# design.net
KiCad netlist of a schematic drawn in EasyEDA Pro
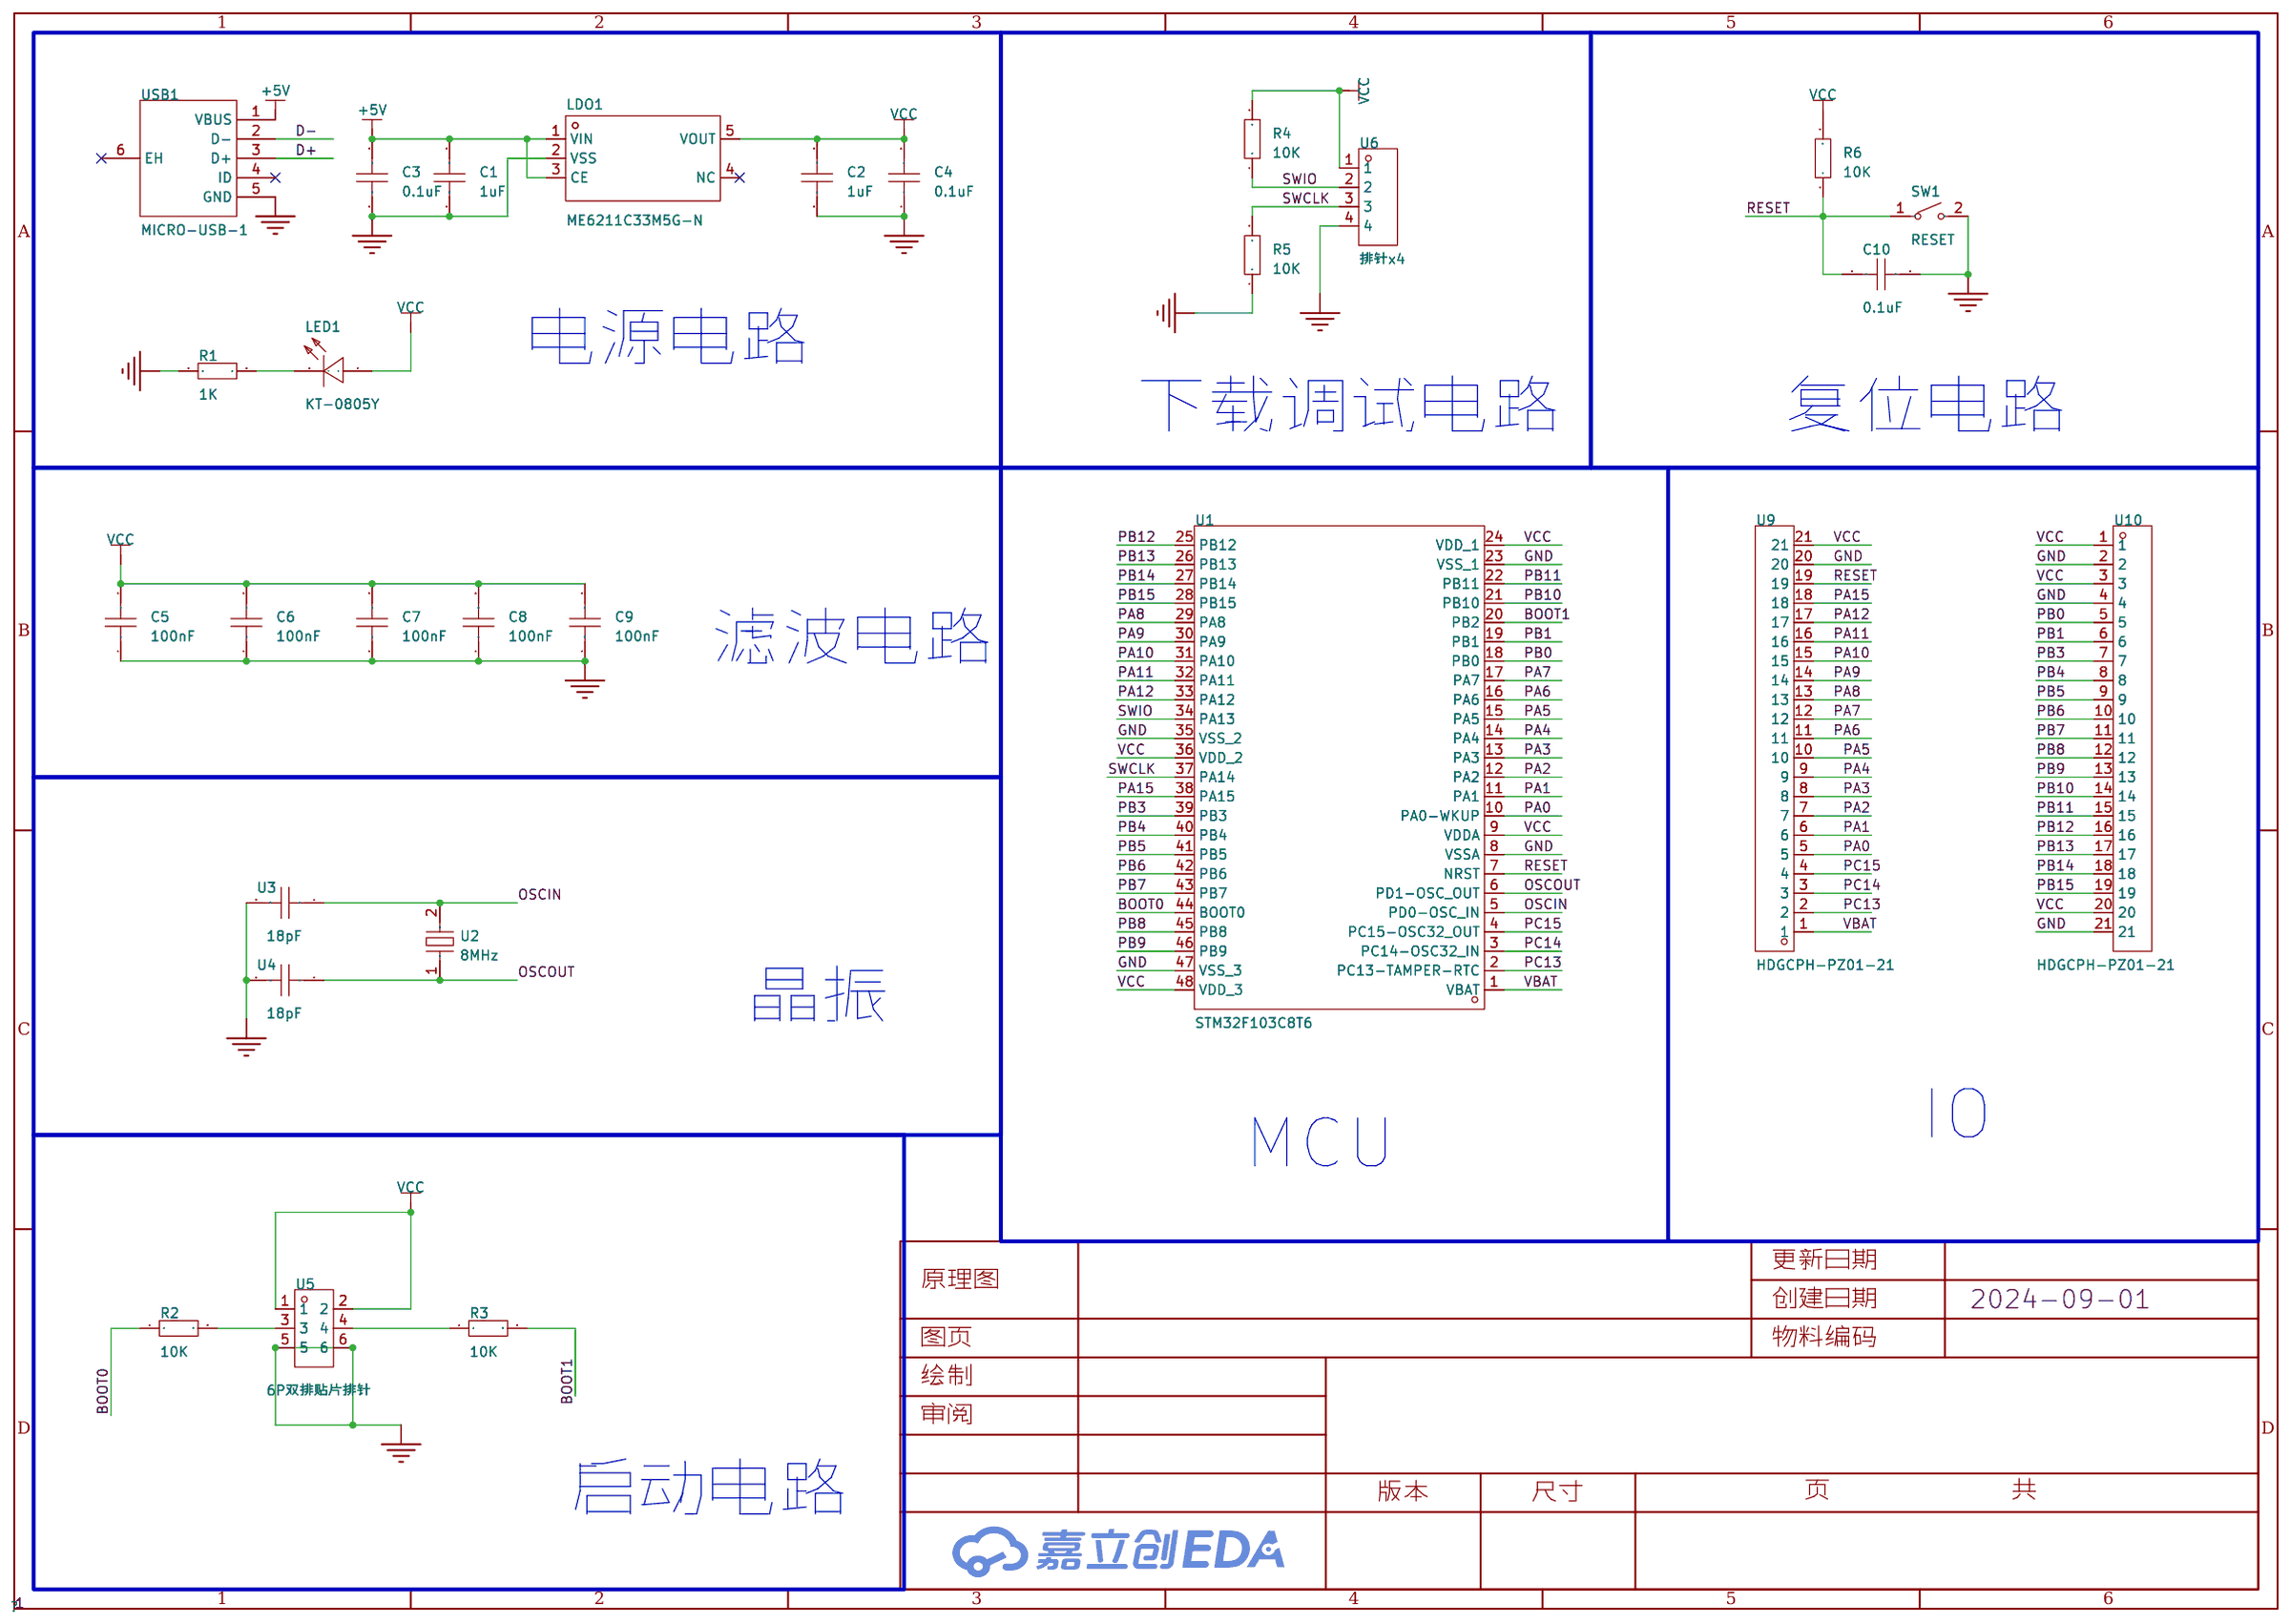
[diagram p0: schematic sheet]

(export (version "E")
  (design (tool "Eeschema 10.0.6"))
  (components
    (comp (ref "C1")
      (value "1uF")
      (footprint "easyedapro:C0603")
      (description "容值:1uF;精度:±10%;额定电压:50V;材质(温度系数):X5R;")
      (fields
        (field (name "Manufacturer Part") "CL10A105KB8NNNC")
        (field (name "Manufacturer") "SAMSUNG(三星)")
      )
      (libsource (lib "easyedapro") (part "CL10A105KB8NNNC"))
    )
    (comp (ref "C2")
      (value "1uF")
      (footprint "easyedapro:C0603")
      (description "容值:1uF;精度:±10%;额定电压:50V;材质(温度系数):X5R;")
      (fields
        (field (name "Manufacturer Part") "CL10A105KB8NNNC")
        (field (name "Manufacturer") "SAMSUNG(三星)")
      )
      (libsource (lib "easyedapro") (part "CL10A105KB8NNNC"))
    )
    (comp (ref "C3")
      (value "0.1uF")
      (footprint "easyedapro:C0603")
      (description "容值:1pF;额定电压:50V;材质(温度系数):C0G;")
      (fields (field (name "Manufacturer Part") "CGJ3E2C0G1H010C080AA") (field (name "Manufacturer") "TDK"))
      (libsource (lib "easyedapro") (part "CGJ3E2C0G1H010C080AA"))
    )
    (comp (ref "C4")
      (value "0.1uF")
      (footprint "easyedapro:C0603")
      (description "容值:1pF;额定电压:50V;材质(温度系数):C0G;")
      (fields (field (name "Manufacturer Part") "CGJ3E2C0G1H010C080AA") (field (name "Manufacturer") "TDK"))
      (libsource (lib "easyedapro") (part "CGJ3E2C0G1H010C080AA"))
    )
    (comp (ref "C5")
      (value "100nF")
      (footprint "easyedapro:C0603")
      (libsource (lib "easyedapro") (part "CapAcitance"))
    )
    (comp (ref "C6")
      (value "100nF")
      (footprint "easyedapro:C0603")
      (libsource (lib "easyedapro") (part "CapAcitance"))
    )
    (comp (ref "C7")
      (value "100nF")
      (footprint "easyedapro:C0603")
      (libsource (lib "easyedapro") (part "CapAcitance"))
    )
    (comp (ref "C8")
      (value "100nF")
      (footprint "easyedapro:C0603")
      (libsource (lib "easyedapro") (part "CapAcitance"))
    )
    (comp (ref "C9")
      (value "100nF")
      (footprint "easyedapro:C0603")
      (libsource (lib "easyedapro") (part "CapAcitance"))
    )
    (comp (ref "C10")
      (value "0.1uF")
      (footprint "easyedapro:C0603")
      (description "容值:1uF;精度:±10%;额定电压:50V;材质(温度系数):X5R;")
      (fields
        (field (name "Manufacturer Part") "CL10A105KB8NNNC")
        (field (name "Manufacturer") "SAMSUNG(三星)")
      )
      (libsource (lib "easyedapro") (part "CL10A105KB8NNNC"))
    )
    (comp (ref "LDO1")
      (value "ME6211C33M5G-N")
      (footprint "easyedapro:SOT-23-5_L3.0-W1.7-P0.95-LS2.8-BL")
      (description "输出类型:固定;最大输入电压:6V;输出电压:3.3V;最大输出电流:500mA;电源纹波抑制比(PSRR):70dB;输出极性:正极;")
      (fields (field (name "Manufacturer") "MICRONE(南京微盟)"))
      (libsource (lib "easyedapro") (part "ME6211C33M5G-N"))
    )
    (comp (ref "LED1")
      (value "KT-0805Y")
      (footprint "easyedapro:LED0805-R-RD")
      (description "发光颜色:黄色;功率:-;正向电流:-;主波长:-;二极管配置:-;透镜颜色:-;色温:-;发光角度:-;载带方式:-;工作温度:-;")
      (fields (field (name "Manufacturer") "KENTO"))
      (libsource (lib "easyedapro") (part "17-21SUYC/TR8"))
    )
    (comp (ref "R1") (value "1K") (footprint "easyedapro:R0603") (libsource (lib "easyedapro") (part "电阻")))
    (comp (ref "R2") (value "10K") (footprint "easyedapro:R0603") (libsource (lib "easyedapro") (part "电阻")))
    (comp (ref "R3") (value "10K") (footprint "easyedapro:R0603") (libsource (lib "easyedapro") (part "电阻")))
    (comp (ref "R4") (value "10K") (footprint "easyedapro:R0603") (libsource (lib "easyedapro") (part "电阻")))
    (comp (ref "R5") (value "10K") (footprint "easyedapro:R0603") (libsource (lib "easyedapro") (part "电阻")))
    (comp (ref "R6") (value "10K") (footprint "easyedapro:R0603") (libsource (lib "easyedapro") (part "电阻")))
    (comp (ref "SW1")
      (value "RESET")
      (footprint "easyedapro:SW-SMD_L6.0-W3.3-LS8.0")
      (libsource (lib "easyedapro") (part "SW_PB2_A1"))
    )
    (comp (ref "U1")
      (value "STM32F103C8T6")
      (footprint "easyedapro:LQFP-48_L7.0-W7.0-P0.50-LS9.0-BL")
      (description "CPU内核:ARM-M3;程序存储容量:64KB;RAM总容量:20KB;GPIO端口数量:37;工作电压范围:2V~3.6V;CPU最大主频:72MHz;程序存储器类型:FLASH;")
      (fields (field (name "Manufacturer") "ST(意法半导体)"))
      (libsource (lib "easyedapro") (part "STM32F103C8T6"))
    )
    (comp (ref "U2")
      (value "8MHz")
      (footprint "easyedapro:HC-49S_L10.6-W4.2-P4.85")
      (description "频率:6.7458MHz;常温频差:±20ppm;外接负载电容:20pF;频率稳定度(全温):±50ppm;")
      (fields
        (field (name "Manufacturer Part") "HY67458M49SOB2T02")
        (field (name "Manufacturer") "Huiyuan crystal(惠源晶工)")
      )
      (libsource (lib "easyedapro") (part "HY67458M49SOB2T02"))
    )
    (comp (ref "U3")
      (value "18pF")
      (footprint "easyedapro:C0603")
      (description "容值:1pF;额定电压:50V;材质(温度系数):C0G;")
      (fields (field (name "Manufacturer Part") "CGJ3E2C0G1H010C080AA") (field (name "Manufacturer") "TDK"))
      (libsource (lib "easyedapro") (part "CGJ3E2C0G1H010C080AA"))
    )
    (comp (ref "U4")
      (value "18pF")
      (footprint "easyedapro:C0603")
      (description "容值:1pF;额定电压:50V;材质(温度系数):C0G;")
      (fields (field (name "Manufacturer Part") "CGJ3E2C0G1H010C080AA") (field (name "Manufacturer") "TDK"))
      (libsource (lib "easyedapro") (part "CGJ3E2C0G1H010C080AA"))
    )
    (comp (ref "U5")
      (value "6P双排贴片排针")
      (footprint "easyedapro:HDR-SMD_6P-P2.54-V-M-R2-C3-LS7.6")
      (libsource (lib "easyedapro") (part "6P双排贴片排针"))
    )
    (comp (ref "U6")
      (value "排针x4")
      (footprint "easyedapro:HDR-TH_4P-P2.54-V-M-1")
      (libsource (lib "easyedapro") (part "排针X4"))
    )
    (comp (ref "U9")
      (value "HDGCPH-PZ01-21")
      (footprint "easyedapro:HDR-TH_21P-P2.54-V-M")
      (fields (field (name "Manufacturer") "HDGC(华德共创)"))
      (libsource (lib "easyedapro") (part "HDGCPH-PZ01- 21"))
    )
    (comp (ref "U10")
      (value "HDGCPH-PZ01-21")
      (footprint "easyedapro:HDR-TH_21P-P2.54-V-M")
      (fields (field (name "Manufacturer") "HDGC(华德共创)"))
      (libsource (lib "easyedapro") (part "HDGCPH-PZ01- 21"))
    )
    (comp (ref "USB1")
      (value "MICRO-USB-1")
      (footprint "easyedapro:MICRO-USB-SMD_C9900008946")
      (libsource (lib "easyedapro") (part "MICRO-USB-1"))
    )
  )
  (nets
    (net (code "1") (name "+5V") (class "Default")
      (node (ref "C1") (pin "2") (pinfunction "2_2") (pintype "unspecified"))
      (node (ref "C3") (pin "2") (pinfunction "2_2") (pintype "unspecified"))
      (node (ref "LDO1") (pin "1") (pinfunction "VIN_1") (pintype "input"))
      (node (ref "LDO1") (pin "3") (pinfunction "CE_3") (pintype "input"))
      (node (ref "USB1") (pin "1") (pinfunction "VBUS_1") (pintype "input"))
    )
    (net (code "2") (name "/BOOT0") (class "Default")
      (node (ref "R2") (pin "1") (pinfunction "1_1") (pintype "input"))
      (node (ref "U1") (pin "44") (pinfunction "BOOT0_44") (pintype "unspecified"))
    )
    (net (code "3") (name "/BOOT1") (class "Default")
      (node (ref "R3") (pin "2") (pinfunction "2_2") (pintype "input"))
      (node (ref "U1") (pin "20") (pinfunction "PB2_20") (pintype "unspecified"))
    )
    (net (code "4") (name "/D+") (class "Default")
      (node (ref "USB1") (pin "3") (pinfunction "D+_3") (pintype "input"))
    )
    (net (code "5") (name "/D-") (class "Default")
      (node (ref "USB1") (pin "2") (pinfunction "D-_2") (pintype "input"))
    )
    (net (code "6") (name "/OSCIN") (class "Default")
      (node (ref "U1") (pin "5") (pinfunction "PD0-OSC_IN_5") (pintype "unspecified"))
      (node (ref "U2") (pin "2") (pinfunction "GND_2") (pintype "input"))
      (node (ref "U3") (pin "1") (pinfunction "1_1") (pintype "unspecified"))
    )
    (net (code "7") (name "/OSCOUT") (class "Default")
      (node (ref "U1") (pin "6") (pinfunction "PD1-OSC_OUT_6") (pintype "unspecified"))
      (node (ref "U2") (pin "1") (pinfunction "1_1") (pintype "input"))
      (node (ref "U4") (pin "1") (pinfunction "1_1") (pintype "unspecified"))
    )
    (net (code "8") (name "/PA0") (class "Default")
      (node (ref "U1") (pin "10") (pinfunction "PA0-WKUP_10") (pintype "unspecified"))
      (node (ref "U9") (pin "5") (pinfunction "5_5") (pintype "unspecified"))
    )
    (net (code "9") (name "/PA1") (class "Default")
      (node (ref "U1") (pin "11") (pinfunction "PA1_11") (pintype "unspecified"))
      (node (ref "U9") (pin "6") (pinfunction "6_6") (pintype "unspecified"))
    )
    (net (code "10") (name "/PA2") (class "Default")
      (node (ref "U1") (pin "12") (pinfunction "PA2_12") (pintype "unspecified"))
      (node (ref "U9") (pin "7") (pinfunction "7_7") (pintype "unspecified"))
    )
    (net (code "11") (name "/PA3") (class "Default")
      (node (ref "U1") (pin "13") (pinfunction "PA3_13") (pintype "unspecified"))
      (node (ref "U9") (pin "8") (pinfunction "8_8") (pintype "unspecified"))
    )
    (net (code "12") (name "/PA4") (class "Default")
      (node (ref "U1") (pin "14") (pinfunction "PA4_14") (pintype "unspecified"))
      (node (ref "U9") (pin "9") (pinfunction "9_9") (pintype "unspecified"))
    )
    (net (code "13") (name "/PA5") (class "Default")
      (node (ref "U1") (pin "15") (pinfunction "PA5_15") (pintype "unspecified"))
      (node (ref "U9") (pin "10") (pinfunction "10_10") (pintype "unspecified"))
    )
    (net (code "14") (name "/PA6") (class "Default")
      (node (ref "U1") (pin "16") (pinfunction "PA6_16") (pintype "unspecified"))
      (node (ref "U9") (pin "11") (pinfunction "11_11") (pintype "unspecified"))
    )
    (net (code "15") (name "/PA7") (class "Default")
      (node (ref "U1") (pin "17") (pinfunction "PA7_17") (pintype "unspecified"))
      (node (ref "U9") (pin "12") (pinfunction "12_12") (pintype "unspecified"))
    )
    (net (code "16") (name "/PA8") (class "Default")
      (node (ref "U1") (pin "29") (pinfunction "PA8_29") (pintype "unspecified"))
      (node (ref "U9") (pin "13") (pinfunction "13_13") (pintype "unspecified"))
    )
    (net (code "17") (name "/PA9") (class "Default")
      (node (ref "U1") (pin "30") (pinfunction "PA9_30") (pintype "unspecified"))
      (node (ref "U9") (pin "14") (pinfunction "14_14") (pintype "unspecified"))
    )
    (net (code "18") (name "/PA10") (class "Default")
      (node (ref "U1") (pin "31") (pinfunction "PA10_31") (pintype "unspecified"))
      (node (ref "U9") (pin "15") (pinfunction "15_15") (pintype "unspecified"))
    )
    (net (code "19") (name "/PA11") (class "Default")
      (node (ref "U1") (pin "32") (pinfunction "PA11_32") (pintype "unspecified"))
      (node (ref "U9") (pin "16") (pinfunction "16_16") (pintype "unspecified"))
    )
    (net (code "20") (name "/PA12") (class "Default")
      (node (ref "U1") (pin "33") (pinfunction "PA12_33") (pintype "unspecified"))
      (node (ref "U9") (pin "17") (pinfunction "17_17") (pintype "unspecified"))
    )
    (net (code "21") (name "/PA15") (class "Default")
      (node (ref "U1") (pin "38") (pinfunction "PA15_38") (pintype "unspecified"))
      (node (ref "U9") (pin "18") (pinfunction "18_18") (pintype "unspecified"))
    )
    (net (code "22") (name "/PB0") (class "Default")
      (node (ref "U1") (pin "18") (pinfunction "PB0_18") (pintype "unspecified"))
      (node (ref "U10") (pin "5") (pinfunction "5_5") (pintype "unspecified"))
    )
    (net (code "23") (name "/PB1") (class "Default")
      (node (ref "U1") (pin "19") (pinfunction "PB1_19") (pintype "unspecified"))
      (node (ref "U10") (pin "6") (pinfunction "6_6") (pintype "unspecified"))
    )
    (net (code "24") (name "/PB3") (class "Default")
      (node (ref "U1") (pin "39") (pinfunction "PB3_39") (pintype "unspecified"))
      (node (ref "U10") (pin "7") (pinfunction "7_7") (pintype "unspecified"))
    )
    (net (code "25") (name "/PB4") (class "Default")
      (node (ref "U1") (pin "40") (pinfunction "PB4_40") (pintype "unspecified"))
      (node (ref "U10") (pin "8") (pinfunction "8_8") (pintype "unspecified"))
    )
    (net (code "26") (name "/PB5") (class "Default")
      (node (ref "U1") (pin "41") (pinfunction "PB5_41") (pintype "unspecified"))
      (node (ref "U10") (pin "9") (pinfunction "9_9") (pintype "unspecified"))
    )
    (net (code "27") (name "/PB6") (class "Default")
      (node (ref "U1") (pin "42") (pinfunction "PB6_42") (pintype "unspecified"))
      (node (ref "U10") (pin "10") (pinfunction "10_10") (pintype "unspecified"))
    )
    (net (code "28") (name "/PB7") (class "Default")
      (node (ref "U1") (pin "43") (pinfunction "PB7_43") (pintype "unspecified"))
      (node (ref "U10") (pin "11") (pinfunction "11_11") (pintype "unspecified"))
    )
    (net (code "29") (name "/PB8") (class "Default")
      (node (ref "U1") (pin "45") (pinfunction "PB8_45") (pintype "unspecified"))
      (node (ref "U10") (pin "12") (pinfunction "12_12") (pintype "unspecified"))
    )
    (net (code "30") (name "/PB9") (class "Default")
      (node (ref "U1") (pin "46") (pinfunction "PB9_46") (pintype "unspecified"))
      (node (ref "U10") (pin "13") (pinfunction "13_13") (pintype "unspecified"))
    )
    (net (code "31") (name "/PB10") (class "Default")
      (node (ref "U1") (pin "21") (pinfunction "PB10_21") (pintype "unspecified"))
      (node (ref "U10") (pin "14") (pinfunction "14_14") (pintype "unspecified"))
    )
    (net (code "32") (name "/PB11") (class "Default")
      (node (ref "U1") (pin "22") (pinfunction "PB11_22") (pintype "unspecified"))
      (node (ref "U10") (pin "15") (pinfunction "15_15") (pintype "unspecified"))
    )
    (net (code "33") (name "/PB12") (class "Default")
      (node (ref "U1") (pin "25") (pinfunction "PB12_25") (pintype "unspecified"))
      (node (ref "U10") (pin "16") (pinfunction "16_16") (pintype "unspecified"))
    )
    (net (code "34") (name "/PB13") (class "Default")
      (node (ref "U1") (pin "26") (pinfunction "PB13_26") (pintype "unspecified"))
      (node (ref "U10") (pin "17") (pinfunction "17_17") (pintype "unspecified"))
    )
    (net (code "35") (name "/PB14") (class "Default")
      (node (ref "U1") (pin "27") (pinfunction "PB14_27") (pintype "unspecified"))
      (node (ref "U10") (pin "18") (pinfunction "18_18") (pintype "unspecified"))
    )
    (net (code "36") (name "/PB15") (class "Default")
      (node (ref "U1") (pin "28") (pinfunction "PB15_28") (pintype "unspecified"))
      (node (ref "U10") (pin "19") (pinfunction "19_19") (pintype "unspecified"))
    )
    (net (code "37") (name "/PC13") (class "Default")
      (node (ref "U1") (pin "2") (pinfunction "PC13-TAMPER-RTC_2") (pintype "unspecified"))
      (node (ref "U9") (pin "2") (pinfunction "2_2") (pintype "unspecified"))
    )
    (net (code "38") (name "/PC14") (class "Default")
      (node (ref "U1") (pin "3") (pinfunction "PC14-OSC32_IN_3") (pintype "unspecified"))
      (node (ref "U9") (pin "3") (pinfunction "3_3") (pintype "unspecified"))
    )
    (net (code "39") (name "/PC15") (class "Default")
      (node (ref "U1") (pin "4") (pinfunction "PC15-OSC32_OUT_4") (pintype "unspecified"))
      (node (ref "U9") (pin "4") (pinfunction "4_4") (pintype "unspecified"))
    )
    (net (code "40") (name "/RESET") (class "Default")
      (node (ref "C10") (pin "1") (pinfunction "1_1") (pintype "unspecified"))
      (node (ref "R6") (pin "1") (pinfunction "1_1") (pintype "input"))
      (node (ref "SW1") (pin "1") (pinfunction "1_1") (pintype "unspecified"))
      (node (ref "U1") (pin "7") (pinfunction "NRST_7") (pintype "unspecified"))
      (node (ref "U9") (pin "19") (pinfunction "19_19") (pintype "unspecified"))
    )
    (net (code "41") (name "/SWCLK") (class "Default")
      (node (ref "R5") (pin "2") (pinfunction "2_2") (pintype "input"))
      (node (ref "U1") (pin "37") (pinfunction "PA14_37") (pintype "unspecified"))
      (node (ref "U6") (pin "3") (pinfunction "3_3") (pintype "unspecified"))
    )
    (net (code "42") (name "/SWIO") (class "Default")
      (node (ref "R4") (pin "1") (pinfunction "1_1") (pintype "input"))
      (node (ref "U1") (pin "34") (pinfunction "PA13_34") (pintype "unspecified"))
      (node (ref "U6") (pin "2") (pinfunction "2_2") (pintype "unspecified"))
    )
    (net (code "43") (name "/VBAT") (class "Default")
      (node (ref "U1") (pin "1") (pinfunction "VBAT_1") (pintype "unspecified"))
      (node (ref "U9") (pin "1") (pinfunction "1_1") (pintype "unspecified"))
    )
    (net (code "44") (name "GND") (class "Default")
      (node (ref "C1") (pin "1") (pinfunction "1_1") (pintype "unspecified"))
      (node (ref "C10") (pin "2") (pinfunction "2_2") (pintype "unspecified"))
      (node (ref "C2") (pin "1") (pinfunction "1_1") (pintype "unspecified"))
      (node (ref "C3") (pin "1") (pinfunction "1_1") (pintype "unspecified"))
      (node (ref "C4") (pin "1") (pinfunction "1_1") (pintype "unspecified"))
      (node (ref "C5") (pin "1") (pinfunction "1_1") (pintype "input"))
      (node (ref "C6") (pin "1") (pinfunction "1_1") (pintype "input"))
      (node (ref "C7") (pin "1") (pinfunction "1_1") (pintype "input"))
      (node (ref "C8") (pin "1") (pinfunction "1_1") (pintype "input"))
      (node (ref "C9") (pin "1") (pinfunction "1_1") (pintype "input"))
      (node (ref "LDO1") (pin "2") (pinfunction "VSS_2") (pintype "input"))
      (node (ref "R1") (pin "1") (pinfunction "1_1") (pintype "input"))
      (node (ref "R5") (pin "1") (pinfunction "1_1") (pintype "input"))
      (node (ref "SW1") (pin "2") (pinfunction "2_2") (pintype "unspecified"))
      (node (ref "U1") (pin "23") (pinfunction "VSS_1_23") (pintype "unspecified"))
      (node (ref "U1") (pin "35") (pinfunction "VSS_2_35") (pintype "unspecified"))
      (node (ref "U1") (pin "47") (pinfunction "VSS_3_47") (pintype "unspecified"))
      (node (ref "U1") (pin "8") (pinfunction "VSSA_8") (pintype "unspecified"))
      (node (ref "U10") (pin "2") (pinfunction "2_2") (pintype "unspecified"))
      (node (ref "U10") (pin "21") (pinfunction "21_21") (pintype "unspecified"))
      (node (ref "U10") (pin "4") (pinfunction "4_4") (pintype "unspecified"))
      (node (ref "U3") (pin "2") (pinfunction "2_2") (pintype "unspecified"))
      (node (ref "U4") (pin "2") (pinfunction "2_2") (pintype "unspecified"))
      (node (ref "U5") (pin "5") (pinfunction "5_5") (pintype "input"))
      (node (ref "U5") (pin "6") (pinfunction "6_6") (pintype "input"))
      (node (ref "U6") (pin "4") (pinfunction "4_4") (pintype "unspecified"))
      (node (ref "U9") (pin "20") (pinfunction "20_20") (pintype "unspecified"))
      (node (ref "USB1") (pin "5") (pinfunction "GND_5") (pintype "input"))
    )
    (net (code "45") (name "Net-(LED1--)") (class "Default")
      (node (ref "LED1") (pin "2") (pinfunction "-_2") (pintype "unspecified"))
      (node (ref "R1") (pin "2") (pinfunction "2_2") (pintype "input"))
    )
    (net (code "46") (name "Net-(R2-Pad2)") (class "Default")
      (node (ref "R2") (pin "2") (pinfunction "2_2") (pintype "input"))
      (node (ref "U5") (pin "3") (pinfunction "3_3") (pintype "input"))
    )
    (net (code "47") (name "Net-(R3-Pad1)") (class "Default")
      (node (ref "R3") (pin "1") (pinfunction "1_1") (pintype "input"))
      (node (ref "U5") (pin "4") (pinfunction "4_4") (pintype "input"))
    )
    (net (code "48") (name "VCC") (class "Default")
      (node (ref "C2") (pin "2") (pinfunction "2_2") (pintype "unspecified"))
      (node (ref "C4") (pin "2") (pinfunction "2_2") (pintype "unspecified"))
      (node (ref "C5") (pin "2") (pinfunction "2_2") (pintype "input"))
      (node (ref "C6") (pin "2") (pinfunction "2_2") (pintype "input"))
      (node (ref "C7") (pin "2") (pinfunction "2_2") (pintype "input"))
      (node (ref "C8") (pin "2") (pinfunction "2_2") (pintype "input"))
      (node (ref "C9") (pin "2") (pinfunction "2_2") (pintype "input"))
      (node (ref "LDO1") (pin "5") (pinfunction "VOUT_5") (pintype "input"))
      (node (ref "LED1") (pin "1") (pinfunction "+_1") (pintype "unspecified"))
      (node (ref "R4") (pin "2") (pinfunction "2_2") (pintype "input"))
      (node (ref "R6") (pin "2") (pinfunction "2_2") (pintype "input"))
      (node (ref "U1") (pin "24") (pinfunction "VDD_1_24") (pintype "unspecified"))
      (node (ref "U1") (pin "36") (pinfunction "VDD_2_36") (pintype "unspecified"))
      (node (ref "U1") (pin "48") (pinfunction "VDD_3_48") (pintype "unspecified"))
      (node (ref "U1") (pin "9") (pinfunction "VDDA_9") (pintype "unspecified"))
      (node (ref "U10") (pin "1") (pinfunction "1_1") (pintype "unspecified"))
      (node (ref "U10") (pin "20") (pinfunction "20_20") (pintype "unspecified"))
      (node (ref "U10") (pin "3") (pinfunction "3_3") (pintype "unspecified"))
      (node (ref "U5") (pin "1") (pinfunction "1_1") (pintype "input"))
      (node (ref "U5") (pin "2") (pinfunction "2_2") (pintype "input"))
      (node (ref "U6") (pin "1") (pinfunction "1_1") (pintype "unspecified"))
      (node (ref "U9") (pin "21") (pinfunction "21_21") (pintype "unspecified"))
    )
    (net (code "49") (name "unconnected-(LDO1-NC-Pad4)") (class "Default")
      (node (ref "LDO1") (pin "4") (pinfunction "NC_4") (pintype "input+no_connect"))
    )
    (net (code "50") (name "unconnected-(USB1-EH-Pad6)") (class "Default")
      (node (ref "USB1") (pin "6") (pinfunction "EH_6") (pintype "input+no_connect"))
    )
    (net (code "51") (name "unconnected-(USB1-ID-Pad4)") (class "Default")
      (node (ref "USB1") (pin "4") (pinfunction "ID_4") (pintype "input+no_connect"))
    )
  )
)
